# 214_oled_1_0_11.net
KiCad netlist of a schematic drawn in EAGLE
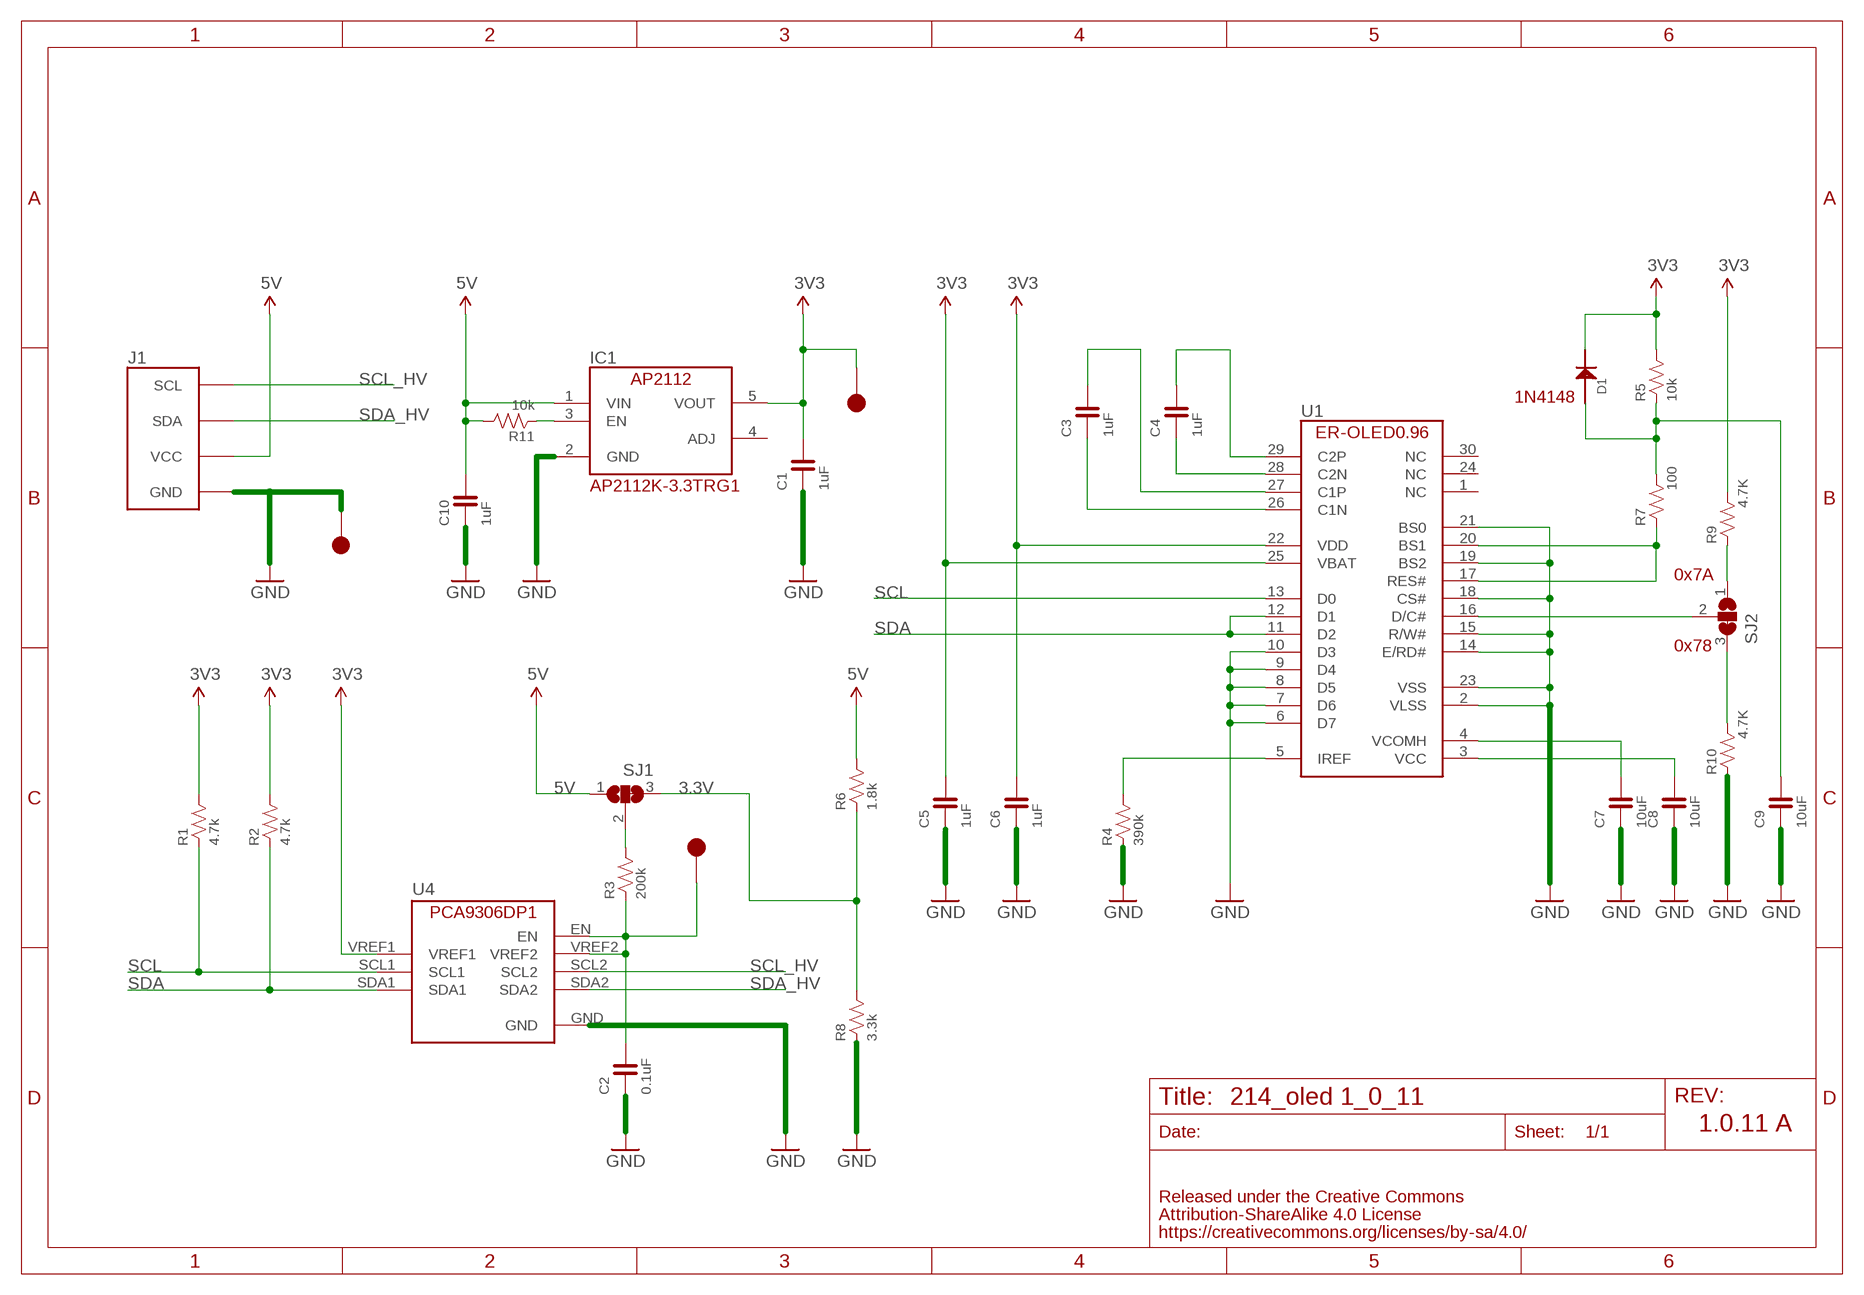
[diagram p0: schematic, sheet 1]

(export (version "E")
  (design (tool "Eeschema 10.0.6"))
  (components
    (comp (ref "C1")
      (value "1uF")
      (footprint "eagle-import:0603")
      (libsource (lib "eagle-import") (part "CAPACITOR-0603"))
    )
    (comp (ref "C2")
      (value "0.1uF")
      (footprint "eagle-import:0603")
      (libsource (lib "eagle-import") (part "CAPACITOR-0603"))
    )
    (comp (ref "C3")
      (value "1uF")
      (footprint "eagle-import:0603")
      (libsource (lib "eagle-import") (part "CAPACITOR-0603"))
    )
    (comp (ref "C4")
      (value "1uF")
      (footprint "eagle-import:0603")
      (libsource (lib "eagle-import") (part "CAPACITOR-0603"))
    )
    (comp (ref "C5")
      (value "1uF")
      (footprint "eagle-import:0603")
      (libsource (lib "eagle-import") (part "CAPACITOR-0603"))
    )
    (comp (ref "C6")
      (value "1uF")
      (footprint "eagle-import:0603")
      (libsource (lib "eagle-import") (part "CAPACITOR-0603"))
    )
    (comp (ref "C7")
      (value "10uF")
      (footprint "eagle-import:0603")
      (libsource (lib "eagle-import") (part "CAPACITOR-0603"))
    )
    (comp (ref "C8")
      (value "10uF")
      (footprint "eagle-import:0603")
      (libsource (lib "eagle-import") (part "CAPACITOR-0603"))
    )
    (comp (ref "C9")
      (value "10uF")
      (footprint "eagle-import:0603")
      (libsource (lib "eagle-import") (part "CAPACITOR-0603"))
    )
    (comp (ref "C10")
      (value "1uF")
      (footprint "eagle-import:0603")
      (libsource (lib "eagle-import") (part "CAPACITOR-0603"))
    )
    (comp (ref "D1")
      (value "1N4148")
      (footprint "eagle-import:1N4148W")
      (libsource (lib "eagle-import") (part "1N4148"))
    )
    (comp (ref "IC1")
      (value "AP2112K-3.3TRG1")
      (footprint "eagle-import:SOT-23-5")
      (libsource (lib "eagle-import") (part "AP2112K-3.3TRG1"))
    )
    (comp (ref "J1")
      (value "FABO_BRICK_I2C-OLED")
      (footprint "eagle-import:FABO_BRICK_I2C_OLED")
      (libsource (lib "eagle-import") (part "FABO_BRICK_I2C-OLED"))
    )
    (comp (ref "R1")
      (value "4.7k")
      (footprint "eagle-import:0603")
      (libsource (lib "eagle-import") (part "RESISTOR-0603"))
    )
    (comp (ref "R2")
      (value "4.7k")
      (footprint "eagle-import:0603")
      (libsource (lib "eagle-import") (part "RESISTOR-0603"))
    )
    (comp (ref "R3")
      (value "200k")
      (footprint "eagle-import:0603")
      (libsource (lib "eagle-import") (part "RESISTOR-0603"))
    )
    (comp (ref "R4")
      (value "390k")
      (footprint "eagle-import:0603")
      (libsource (lib "eagle-import") (part "RESISTOR-0603"))
    )
    (comp (ref "R5")
      (value "10k")
      (footprint "eagle-import:0603")
      (libsource (lib "eagle-import") (part "RESISTOR-0603"))
    )
    (comp (ref "R6")
      (value "1.8k")
      (footprint "eagle-import:0603")
      (libsource (lib "eagle-import") (part "RESISTOR-0603"))
    )
    (comp (ref "R7")
      (value "100")
      (footprint "eagle-import:0603")
      (libsource (lib "eagle-import") (part "RESISTOR-0603"))
    )
    (comp (ref "R8")
      (value "3.3k")
      (footprint "eagle-import:0603")
      (libsource (lib "eagle-import") (part "RESISTOR-0603"))
    )
    (comp (ref "R9")
      (value "4.7K")
      (footprint "eagle-import:0603")
      (libsource (lib "eagle-import") (part "RESISTOR-0603"))
    )
    (comp (ref "R10")
      (value "4.7K")
      (footprint "eagle-import:0603")
      (libsource (lib "eagle-import") (part "RESISTOR-0603"))
    )
    (comp (ref "R11")
      (value "10k")
      (footprint "eagle-import:0603")
      (libsource (lib "eagle-import") (part "RESISTOR-0603"))
    )
    (comp (ref "SJ1")
      (value "SJ2W")
      (footprint "eagle-import:SJ_2")
      (libsource (lib "eagle-import") (part "SJ2W"))
    )
    (comp (ref "SJ2")
      (value "SJ2W")
      (footprint "eagle-import:SJ_2")
      (libsource (lib "eagle-import") (part "SJ2W"))
    )
    (comp (ref "TP1")
      (value "TP-15")
      (footprint "eagle-import:TP-15")
      (libsource (lib "eagle-import") (part "TP-15"))
    )
    (comp (ref "TP2")
      (value "TP-15")
      (footprint "eagle-import:TP-15")
      (libsource (lib "eagle-import") (part "TP-15"))
    )
    (comp (ref "TP5")
      (value "TP-15")
      (footprint "eagle-import:TP-15")
      (libsource (lib "eagle-import") (part "TP-15"))
    )
    (comp (ref "U1")
      (value "ER-OLED0.96-1ER-CON30HT-1")
      (footprint "eagle-import:ER-CON30HT-1")
      (libsource (lib "eagle-import") (part "ER-OLED0.96-1ER-CON30HT-1"))
    )
    (comp (ref "U4")
      (value "PCA9306DP1")
      (footprint "eagle-import:TSSOP8")
      (libsource (lib "eagle-import") (part "PCA9306DP1"))
    )
  )
  (nets
    (net (code "1") (name "/3.3V") (class "Default")
      (node (ref "R6") (pin "1") (pinfunction "1_1") (pintype "bidirectional"))
      (node (ref "R8") (pin "2") (pinfunction "2_2") (pintype "bidirectional"))
      (node (ref "SJ1") (pin "3") (pinfunction "3_3") (pintype "passive"))
    )
    (net (code "2") (name "/SCL") (class "Default")
      (node (ref "R1") (pin "1") (pinfunction "1_1") (pintype "bidirectional"))
      (node (ref "U1") (pin "13") (pinfunction "D0_13") (pintype "bidirectional"))
      (node (ref "U4") (pin "SCL1") (pinfunction "SCL1_SCL1") (pintype "bidirectional"))
    )
    (net (code "3") (name "/SCL_HV") (class "Default")
      (node (ref "J1") (pin "SCL") (pinfunction "SCL_SCL") (pintype "bidirectional"))
      (node (ref "U4") (pin "SCL2") (pinfunction "SCL2_SCL2") (pintype "bidirectional"))
    )
    (net (code "4") (name "/SDA") (class "Default")
      (node (ref "R2") (pin "1") (pinfunction "1_1") (pintype "bidirectional"))
      (node (ref "U1") (pin "11") (pinfunction "D2_11") (pintype "bidirectional"))
      (node (ref "U1") (pin "12") (pinfunction "D1_12") (pintype "bidirectional"))
      (node (ref "U4") (pin "SDA1") (pinfunction "SDA1_SDA1") (pintype "bidirectional"))
    )
    (net (code "5") (name "/SDA_HV") (class "Default")
      (node (ref "J1") (pin "SDA") (pinfunction "SDA_SDA") (pintype "bidirectional"))
      (node (ref "U4") (pin "SDA2") (pinfunction "SDA2_SDA2") (pintype "bidirectional"))
    )
    (net (code "6") (name "3V3") (class "Default")
      (node (ref "C1") (pin "2") (pinfunction "2_2") (pintype "passive"))
      (node (ref "C5") (pin "2") (pinfunction "2_2") (pintype "passive"))
      (node (ref "C6") (pin "2") (pinfunction "2_2") (pintype "passive"))
      (node (ref "D1") (pin "CATHODE") (pinfunction "CATHODE_CATHODE") (pintype "bidirectional"))
      (node (ref "IC1") (pin "5") (pinfunction "VOUT_5") (pintype "bidirectional"))
      (node (ref "R1") (pin "2") (pinfunction "2_2") (pintype "bidirectional"))
      (node (ref "R2") (pin "2") (pinfunction "2_2") (pintype "bidirectional"))
      (node (ref "R5") (pin "2") (pinfunction "2_2") (pintype "bidirectional"))
      (node (ref "R9") (pin "2") (pinfunction "2_2") (pintype "bidirectional"))
      (node (ref "TP5") (pin "1") (pinfunction "1_1") (pintype "bidirectional"))
      (node (ref "U1") (pin "22") (pinfunction "VDD_22") (pintype "bidirectional"))
      (node (ref "U1") (pin "25") (pinfunction "VBAT_25") (pintype "bidirectional"))
      (node (ref "U4") (pin "VREF1") (pinfunction "VREF1_VREF1") (pintype "bidirectional"))
    )
    (net (code "7") (name "5V") (class "Default")
      (node (ref "C10") (pin "2") (pinfunction "2_2") (pintype "passive"))
      (node (ref "IC1") (pin "1") (pinfunction "VIN_1") (pintype "bidirectional"))
      (node (ref "J1") (pin "VCC") (pinfunction "VCC_VCC") (pintype "bidirectional"))
      (node (ref "R11") (pin "2") (pinfunction "2_2") (pintype "bidirectional"))
      (node (ref "R6") (pin "2") (pinfunction "2_2") (pintype "bidirectional"))
      (node (ref "SJ1") (pin "1") (pinfunction "1_1") (pintype "passive"))
    )
    (net (code "8") (name "GND") (class "Default")
      (node (ref "C1") (pin "1") (pinfunction "1_1") (pintype "passive"))
      (node (ref "C10") (pin "1") (pinfunction "1_1") (pintype "passive"))
      (node (ref "C2") (pin "1") (pinfunction "1_1") (pintype "passive"))
      (node (ref "C5") (pin "1") (pinfunction "1_1") (pintype "passive"))
      (node (ref "C6") (pin "1") (pinfunction "1_1") (pintype "passive"))
      (node (ref "C7") (pin "1") (pinfunction "1_1") (pintype "passive"))
      (node (ref "C8") (pin "1") (pinfunction "1_1") (pintype "passive"))
      (node (ref "C9") (pin "1") (pinfunction "1_1") (pintype "passive"))
      (node (ref "IC1") (pin "2") (pinfunction "GND_2") (pintype "bidirectional"))
      (node (ref "J1") (pin "GND") (pinfunction "GND_GND") (pintype "bidirectional"))
      (node (ref "R10") (pin "1") (pinfunction "1_1") (pintype "bidirectional"))
      (node (ref "R4") (pin "1") (pinfunction "1_1") (pintype "bidirectional"))
      (node (ref "R8") (pin "1") (pinfunction "1_1") (pintype "bidirectional"))
      (node (ref "TP1") (pin "1") (pinfunction "1_1") (pintype "bidirectional"))
      (node (ref "U1") (pin "10") (pinfunction "D3_10") (pintype "bidirectional"))
      (node (ref "U1") (pin "14") (pinfunction "E/RD#_14") (pintype "bidirectional"))
      (node (ref "U1") (pin "15") (pinfunction "R/W#_15") (pintype "bidirectional"))
      (node (ref "U1") (pin "18") (pinfunction "CS#_18") (pintype "bidirectional"))
      (node (ref "U1") (pin "19") (pinfunction "BS2_19") (pintype "bidirectional"))
      (node (ref "U1") (pin "2") (pinfunction "VLSS_2") (pintype "bidirectional"))
      (node (ref "U1") (pin "21") (pinfunction "BS0_21") (pintype "bidirectional"))
      (node (ref "U1") (pin "23") (pinfunction "VSS_23") (pintype "bidirectional"))
      (node (ref "U1") (pin "6") (pinfunction "D7_6") (pintype "bidirectional"))
      (node (ref "U1") (pin "7") (pinfunction "D6_7") (pintype "bidirectional"))
      (node (ref "U1") (pin "8") (pinfunction "D5_8") (pintype "bidirectional"))
      (node (ref "U1") (pin "9") (pinfunction "D4_9") (pintype "bidirectional"))
      (node (ref "U4") (pin "GND") (pinfunction "GND_GND") (pintype "bidirectional"))
    )
    (net (code "9") (name "Net-(C2-Pad2)") (class "Default")
      (node (ref "C2") (pin "2") (pinfunction "2_2") (pintype "passive"))
      (node (ref "R3") (pin "1") (pinfunction "1_1") (pintype "bidirectional"))
      (node (ref "TP2") (pin "1") (pinfunction "1_1") (pintype "bidirectional"))
      (node (ref "U4") (pin "EN") (pinfunction "EN_EN") (pintype "bidirectional"))
      (node (ref "U4") (pin "VREF2") (pinfunction "VREF2_VREF2") (pintype "bidirectional"))
    )
    (net (code "10") (name "Net-(C9-Pad2)") (class "Default")
      (node (ref "C9") (pin "2") (pinfunction "2_2") (pintype "passive"))
      (node (ref "D1") (pin "ANODE") (pinfunction "ANODE_ANODE") (pintype "bidirectional"))
      (node (ref "R5") (pin "1") (pinfunction "1_1") (pintype "bidirectional"))
      (node (ref "R7") (pin "2") (pinfunction "2_2") (pintype "bidirectional"))
    )
    (net (code "11") (name "Net-(IC1-EN)") (class "Default")
      (node (ref "IC1") (pin "3") (pinfunction "EN_3") (pintype "bidirectional"))
      (node (ref "R11") (pin "1") (pinfunction "1_1") (pintype "bidirectional"))
    )
    (net (code "12") (name "Net-(R3-Pad2)") (class "Default")
      (node (ref "R3") (pin "2") (pinfunction "2_2") (pintype "bidirectional"))
      (node (ref "SJ1") (pin "2") (pinfunction "2_2") (pintype "passive"))
    )
    (net (code "13") (name "Net-(R9-Pad1)") (class "Default")
      (node (ref "R9") (pin "1") (pinfunction "1_1") (pintype "bidirectional"))
      (node (ref "SJ2") (pin "1") (pinfunction "1_1") (pintype "passive"))
    )
    (net (code "14") (name "Net-(R10-Pad2)") (class "Default")
      (node (ref "R10") (pin "2") (pinfunction "2_2") (pintype "bidirectional"))
      (node (ref "SJ2") (pin "3") (pinfunction "3_3") (pintype "passive"))
    )
    (net (code "15") (name "Net-(U1-BS1)") (class "Default")
      (node (ref "R7") (pin "1") (pinfunction "1_1") (pintype "bidirectional"))
      (node (ref "U1") (pin "17") (pinfunction "RES#_17") (pintype "bidirectional"))
      (node (ref "U1") (pin "20") (pinfunction "BS1_20") (pintype "bidirectional"))
    )
    (net (code "16") (name "Net-(U1-C1N)") (class "Default")
      (node (ref "C3") (pin "1") (pinfunction "1_1") (pintype "passive"))
      (node (ref "U1") (pin "26") (pinfunction "C1N_26") (pintype "bidirectional"))
    )
    (net (code "17") (name "Net-(U1-C1P)") (class "Default")
      (node (ref "C3") (pin "2") (pinfunction "2_2") (pintype "passive"))
      (node (ref "U1") (pin "27") (pinfunction "C1P_27") (pintype "bidirectional"))
    )
    (net (code "18") (name "Net-(U1-C2N)") (class "Default")
      (node (ref "C4") (pin "1") (pinfunction "1_1") (pintype "passive"))
      (node (ref "U1") (pin "28") (pinfunction "C2N_28") (pintype "bidirectional"))
    )
    (net (code "19") (name "Net-(U1-C2P)") (class "Default")
      (node (ref "C4") (pin "2") (pinfunction "2_2") (pintype "passive"))
      (node (ref "U1") (pin "29") (pinfunction "C2P_29") (pintype "bidirectional"))
    )
    (net (code "20") (name "Net-(U1-D{slash}C#)") (class "Default")
      (node (ref "SJ2") (pin "2") (pinfunction "2_2") (pintype "passive"))
      (node (ref "U1") (pin "16") (pinfunction "D/C#_16") (pintype "bidirectional"))
    )
    (net (code "21") (name "Net-(U1-IREF)") (class "Default")
      (node (ref "R4") (pin "2") (pinfunction "2_2") (pintype "bidirectional"))
      (node (ref "U1") (pin "5") (pinfunction "IREF_5") (pintype "bidirectional"))
    )
    (net (code "22") (name "Net-(U1-VCC)") (class "Default")
      (node (ref "C8") (pin "2") (pinfunction "2_2") (pintype "passive"))
      (node (ref "U1") (pin "3") (pinfunction "VCC_3") (pintype "bidirectional"))
    )
    (net (code "23") (name "Net-(U1-VCOMH)") (class "Default")
      (node (ref "C7") (pin "2") (pinfunction "2_2") (pintype "passive"))
      (node (ref "U1") (pin "4") (pinfunction "VCOMH_4") (pintype "bidirectional"))
    )
    (net (code "24") (name "unconnected-(IC1-ADJ-Pad4)") (class "Default")
      (node (ref "IC1") (pin "4") (pinfunction "ADJ_4") (pintype "bidirectional"))
    )
    (net (code "25") (name "unconnected-(U1-NC-Pad1)") (class "Default")
      (node (ref "U1") (pin "1") (pinfunction "NC_1") (pintype "bidirectional"))
    )
    (net (code "26") (name "unconnected-(U1-NC-Pad24)") (class "Default")
      (node (ref "U1") (pin "24") (pinfunction "NC_24") (pintype "bidirectional"))
    )
    (net (code "27") (name "unconnected-(U1-NC-Pad30)") (class "Default")
      (node (ref "U1") (pin "30") (pinfunction "NC_30") (pintype "bidirectional"))
    )
  )
)
